# sensormodule.net
KiCad netlist of a schematic drawn in Altium Designer
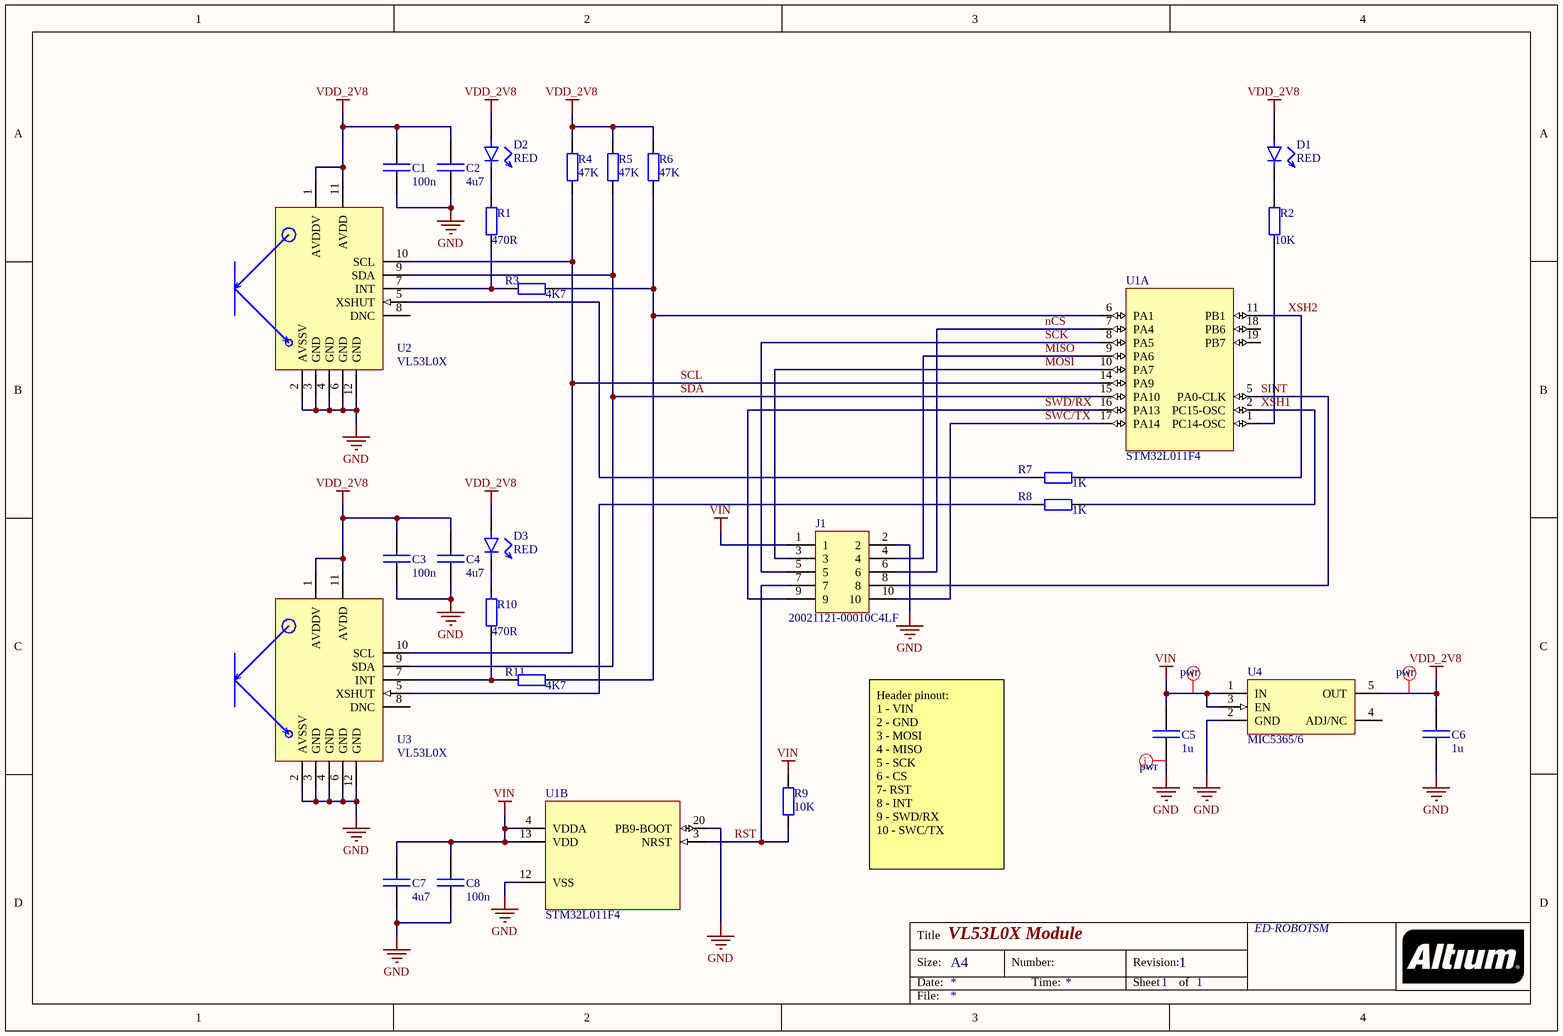
[diagram p0: sensormodule.SchDoc]

(export (version "E")
  (design (tool "Eeschema 10.0.6"))
  (components
    (comp (ref "C1")
      (value "100n")
      (footprint "CAPC1005X06N")
      (description "Capacitor")
      (fields (field (name "Comment") "cap"))
      (libsource (lib "lib_passives") (part "cap"))
    )
    (comp (ref "C2")
      (value "4u7")
      (footprint "CAPC2012X11N")
      (description "Capacitor")
      (fields (field (name "Comment") "cap"))
      (libsource (lib "lib_passives") (part "cap"))
    )
    (comp (ref "C3")
      (value "100n")
      (footprint "CAPC1005X06N")
      (description "Capacitor")
      (fields (field (name "Comment") "cap"))
      (libsource (lib "lib_passives") (part "cap"))
    )
    (comp (ref "C4")
      (value "4u7")
      (footprint "CAPC2012X11N")
      (description "Capacitor")
      (fields (field (name "Comment") "cap"))
      (libsource (lib "lib_passives") (part "cap"))
    )
    (comp (ref "C5")
      (value "1u")
      (footprint "CAPC1005X06N")
      (description "Capacitor")
      (fields (field (name "Comment") "cap"))
      (libsource (lib "lib_passives") (part "cap"))
    )
    (comp (ref "C6")
      (value "1u")
      (footprint "CAPC1005X06N")
      (description "Capacitor")
      (fields (field (name "Comment") "cap"))
      (libsource (lib "lib_passives") (part "cap"))
    )
    (comp (ref "C7")
      (value "4u7")
      (footprint "CAPC2012X11N")
      (description "Capacitor")
      (fields (field (name "Comment") "cap"))
      (libsource (lib "lib_passives") (part "cap"))
    )
    (comp (ref "C8")
      (value "100n")
      (footprint "CAPC1005X06N")
      (description "Capacitor")
      (fields (field (name "Comment") "cap"))
      (libsource (lib "lib_passives") (part "cap"))
    )
    (comp (ref "D1")
      (value "RED")
      (footprint "CAPCP1005X06N")
      (description "LED")
      (fields (field (name "Comment") "led"))
      (libsource (lib "lib_actives") (part "led"))
    )
    (comp (ref "D2")
      (value "RED")
      (footprint "CAPCP1005X06N")
      (description "LED")
      (fields (field (name "Comment") "led"))
      (libsource (lib "lib_actives") (part "led"))
    )
    (comp (ref "D3")
      (value "RED")
      (footprint "CAPCP1005X06N")
      (description "LED")
      (fields (field (name "Comment") "led"))
      (libsource (lib "lib_actives") (part "led"))
    )
    (comp (ref "J1")
      (value "20021121-00010C4LF")
      (footprint "hdr_2x5_50mil")
      (description "2x5 Header")
      (libsource (lib "lib_connectors") (part "hdr_2x5"))
    )
    (comp (ref "R1")
      (value "470R")
      (footprint "RESC1005X04N")
      (description "Resistor")
      (fields (field (name "Comment") "res"))
      (libsource (lib "lib_passives") (part "res"))
    )
    (comp (ref "R2")
      (value "10K")
      (footprint "RESC1005X04N")
      (description "Resistor")
      (fields (field (name "Comment") "res"))
      (libsource (lib "lib_passives") (part "res"))
    )
    (comp (ref "R3")
      (value "4K7")
      (footprint "RESC1005X04N")
      (description "Resistor")
      (fields (field (name "Comment") "res"))
      (libsource (lib "") (part "res_1"))
    )
    (comp (ref "R4")
      (value "47K")
      (footprint "RESC1005X04N")
      (description "Resistor")
      (fields (field (name "Comment") "res"))
      (libsource (lib "lib_passives") (part "res"))
    )
    (comp (ref "R5")
      (value "47K")
      (footprint "RESC1005X04N")
      (description "Resistor")
      (fields (field (name "Comment") "res"))
      (libsource (lib "lib_passives") (part "res"))
    )
    (comp (ref "R6")
      (value "47K")
      (footprint "RESC1005X04N")
      (description "Resistor")
      (fields (field (name "Comment") "res"))
      (libsource (lib "lib_passives") (part "res"))
    )
    (comp (ref "R7")
      (value "1K")
      (footprint "RESC1005X04N")
      (description "Resistor")
      (fields (field (name "Comment") "res"))
      (libsource (lib "") (part "res_1"))
    )
    (comp (ref "R8")
      (value "1K")
      (footprint "RESC1005X04N")
      (description "Resistor")
      (fields (field (name "Comment") "res"))
      (libsource (lib "") (part "res_1"))
    )
    (comp (ref "R9")
      (value "10K")
      (footprint "RESC1005X04N")
      (description "Resistor")
      (fields (field (name "Comment") "res"))
      (libsource (lib "lib_passives") (part "res"))
    )
    (comp (ref "R10")
      (value "470R")
      (footprint "RESC1005X04N")
      (description "Resistor")
      (fields (field (name "Comment") "res"))
      (libsource (lib "lib_passives") (part "res"))
    )
    (comp (ref "R11")
      (value "4K7")
      (footprint "RESC1005X04N")
      (description "Resistor")
      (fields (field (name "Comment") "res"))
      (libsource (lib "") (part "res_1"))
    )
    (comp (ref "U1")
      (value "STM32L011F4")
      (footprint "QFN50P300X300X60-20N")
      (libsource (lib "lib_st") (part "stm32l011f4u"))
    )
    (comp (ref "U2")
      (value "VL53L0X")
      (footprint "LGA12C80P3X5_240X440X105")
      (description "vl53l0x ToF sensor")
      (libsource (lib "sensormodule") (part "vl53l0x"))
    )
    (comp (ref "U3")
      (value "VL53L0X")
      (footprint "LGA12C80P3X5_240X440X105")
      (description "vl53l0x ToF sensor")
      (libsource (lib "sensormodule") (part "vl53l0x"))
    )
    (comp (ref "U4")
      (value "MIC5365/6")
      (footprint "SOT65P210X110-5N")
      (description "5pin voltage regulator")
      (libsource (lib "lib_microchip") (part "mic5365"))
    )
  )
  (nets
    (net (code "1") (name "/MISO") (class "Default")
      (node (ref "J1") (pin "4") (pinfunction "4_4") (pintype "passive"))
      (node (ref "U1") (pin "9") (pinfunction "PA6_9") (pintype "bidirectional"))
    )
    (net (code "2") (name "/MOSI") (class "Default")
      (node (ref "J1") (pin "3") (pinfunction "3_3") (pintype "passive"))
      (node (ref "U1") (pin "10") (pinfunction "PA7_10") (pintype "bidirectional"))
    )
    (net (code "3") (name "/RST") (class "Default")
      (node (ref "J1") (pin "7") (pinfunction "7_7") (pintype "passive"))
      (node (ref "R9") (pin "1") (pinfunction "1_1") (pintype "passive"))
      (node (ref "U1") (pin "3") (pinfunction "NRST_3") (pintype "input"))
    )
    (net (code "4") (name "/SCK") (class "Default")
      (node (ref "J1") (pin "5") (pinfunction "5_5") (pintype "passive"))
      (node (ref "U1") (pin "8") (pinfunction "PA5_8") (pintype "bidirectional"))
    )
    (net (code "5") (name "/SCL") (class "Default")
      (node (ref "R4") (pin "1") (pinfunction "1_1") (pintype "passive"))
      (node (ref "U1") (pin "14") (pinfunction "PA9_14") (pintype "bidirectional"))
      (node (ref "U2") (pin "10") (pinfunction "SCL_10") (pintype "open_collector"))
      (node (ref "U3") (pin "10") (pinfunction "SCL_10") (pintype "open_collector"))
    )
    (net (code "6") (name "/SDA") (class "Default")
      (node (ref "R5") (pin "1") (pinfunction "1_1") (pintype "passive"))
      (node (ref "U1") (pin "15") (pinfunction "PA10_15") (pintype "bidirectional"))
      (node (ref "U2") (pin "9") (pinfunction "SDA_9") (pintype "open_collector"))
      (node (ref "U3") (pin "9") (pinfunction "SDA_9") (pintype "open_collector"))
    )
    (net (code "7") (name "/SINT") (class "Default")
      (node (ref "J1") (pin "8") (pinfunction "8_8") (pintype "passive"))
      (node (ref "U1") (pin "5") (pinfunction "PA0-CLK_5") (pintype "bidirectional"))
    )
    (net (code "8") (name "/SWC{slash}TX") (class "Default")
      (node (ref "J1") (pin "10") (pinfunction "10_10") (pintype "passive"))
      (node (ref "U1") (pin "17") (pinfunction "PA14_17") (pintype "bidirectional"))
    )
    (net (code "9") (name "/SWD{slash}RX") (class "Default")
      (node (ref "J1") (pin "9") (pinfunction "9_9") (pintype "passive"))
      (node (ref "U1") (pin "16") (pinfunction "PA13_16") (pintype "bidirectional"))
    )
    (net (code "10") (name "/XSH1") (class "Default")
      (node (ref "R8") (pin "1") (pinfunction "1_1") (pintype "passive"))
      (node (ref "U1") (pin "2") (pinfunction "PC15-OSC_2") (pintype "bidirectional"))
    )
    (net (code "11") (name "/XSH2") (class "Default")
      (node (ref "R7") (pin "1") (pinfunction "1_1") (pintype "passive"))
      (node (ref "U1") (pin "11") (pinfunction "PB1_11") (pintype "bidirectional"))
    )
    (net (code "12") (name "/nCS") (class "Default")
      (node (ref "J1") (pin "6") (pinfunction "6_6") (pintype "passive"))
      (node (ref "U1") (pin "7") (pinfunction "PA4_7") (pintype "bidirectional"))
    )
    (net (code "13") (name "GND") (class "Default")
      (node (ref "C1") (pin "1") (pinfunction "1_1") (pintype "passive"))
      (node (ref "C2") (pin "1") (pinfunction "1_1") (pintype "passive"))
      (node (ref "C3") (pin "1") (pinfunction "1_1") (pintype "passive"))
      (node (ref "C4") (pin "1") (pinfunction "1_1") (pintype "passive"))
      (node (ref "C5") (pin "1") (pinfunction "1_1") (pintype "passive"))
      (node (ref "C6") (pin "1") (pinfunction "1_1") (pintype "passive"))
      (node (ref "C7") (pin "1") (pinfunction "1_1") (pintype "passive"))
      (node (ref "C8") (pin "1") (pinfunction "1_1") (pintype "passive"))
      (node (ref "J1") (pin "2") (pinfunction "2_2") (pintype "passive"))
      (node (ref "U1") (pin "12") (pinfunction "VSS_12") (pintype "power_in"))
      (node (ref "U1") (pin "20") (pinfunction "PB9-BOOT_20") (pintype "bidirectional"))
      (node (ref "U2") (pin "12") (pinfunction "GND_12") (pintype "power_in"))
      (node (ref "U2") (pin "2") (pinfunction "AVSSV_2") (pintype "power_in"))
      (node (ref "U2") (pin "3") (pinfunction "GND_3") (pintype "power_in"))
      (node (ref "U2") (pin "4") (pinfunction "GND_4") (pintype "power_in"))
      (node (ref "U2") (pin "6") (pinfunction "GND_6") (pintype "power_in"))
      (node (ref "U3") (pin "12") (pinfunction "GND_12") (pintype "power_in"))
      (node (ref "U3") (pin "2") (pinfunction "AVSSV_2") (pintype "power_in"))
      (node (ref "U3") (pin "3") (pinfunction "GND_3") (pintype "power_in"))
      (node (ref "U3") (pin "4") (pinfunction "GND_4") (pintype "power_in"))
      (node (ref "U3") (pin "6") (pinfunction "GND_6") (pintype "power_in"))
      (node (ref "U4") (pin "2") (pinfunction "GND_2") (pintype "power_in"))
    )
    (net (code "14") (name "Net-(D1-PadC)") (class "Default")
      (node (ref "D1") (pin "C") (pinfunction "C_C") (pintype "passive"))
      (node (ref "R2") (pin "2") (pinfunction "2_2") (pintype "passive"))
    )
    (net (code "15") (name "Net-(D2-PadC)") (class "Default")
      (node (ref "D2") (pin "C") (pinfunction "C_C") (pintype "passive"))
      (node (ref "R1") (pin "2") (pinfunction "2_2") (pintype "passive"))
    )
    (net (code "16") (name "Net-(D3-PadC)") (class "Default")
      (node (ref "D3") (pin "C") (pinfunction "C_C") (pintype "passive"))
      (node (ref "R10") (pin "2") (pinfunction "2_2") (pintype "passive"))
    )
    (net (code "17") (name "Net-(U1A-PA1)") (class "Default")
      (node (ref "R11") (pin "1") (pinfunction "1_1") (pintype "passive"))
      (node (ref "R3") (pin "1") (pinfunction "1_1") (pintype "passive"))
      (node (ref "R6") (pin "1") (pinfunction "1_1") (pintype "passive"))
      (node (ref "U1") (pin "6") (pinfunction "PA1_6") (pintype "bidirectional"))
    )
    (net (code "18") (name "Net-(U1A-PC14-OSC)") (class "Default")
      (node (ref "R2") (pin "1") (pinfunction "1_1") (pintype "passive"))
      (node (ref "U1") (pin "1") (pinfunction "PC14-OSC_1") (pintype "bidirectional"))
    )
    (net (code "19") (name "Net-(U2-INT)") (class "Default")
      (node (ref "R1") (pin "1") (pinfunction "1_1") (pintype "passive"))
      (node (ref "R3") (pin "2") (pinfunction "2_2") (pintype "passive"))
      (node (ref "U2") (pin "7") (pinfunction "INT_7") (pintype "open_collector"))
    )
    (net (code "20") (name "Net-(U2-XSHUT)") (class "Default")
      (node (ref "R7") (pin "2") (pinfunction "2_2") (pintype "passive"))
      (node (ref "U2") (pin "5") (pinfunction "XSHUT_5") (pintype "input"))
    )
    (net (code "21") (name "Net-(U3-INT)") (class "Default")
      (node (ref "R10") (pin "1") (pinfunction "1_1") (pintype "passive"))
      (node (ref "R11") (pin "2") (pinfunction "2_2") (pintype "passive"))
      (node (ref "U3") (pin "7") (pinfunction "INT_7") (pintype "open_collector"))
    )
    (net (code "22") (name "Net-(U3-XSHUT)") (class "Default")
      (node (ref "R8") (pin "2") (pinfunction "2_2") (pintype "passive"))
      (node (ref "U3") (pin "5") (pinfunction "XSHUT_5") (pintype "input"))
    )
    (net (code "23") (name "VDD_2V8") (class "Default")
      (node (ref "C1") (pin "2") (pinfunction "2_2") (pintype "passive"))
      (node (ref "C2") (pin "2") (pinfunction "2_2") (pintype "passive"))
      (node (ref "C3") (pin "2") (pinfunction "2_2") (pintype "passive"))
      (node (ref "C4") (pin "2") (pinfunction "2_2") (pintype "passive"))
      (node (ref "C6") (pin "2") (pinfunction "2_2") (pintype "passive"))
      (node (ref "D1") (pin "A") (pinfunction "A_A") (pintype "passive"))
      (node (ref "D2") (pin "A") (pinfunction "A_A") (pintype "passive"))
      (node (ref "D3") (pin "A") (pinfunction "A_A") (pintype "passive"))
      (node (ref "R4") (pin "2") (pinfunction "2_2") (pintype "passive"))
      (node (ref "R5") (pin "2") (pinfunction "2_2") (pintype "passive"))
      (node (ref "R6") (pin "2") (pinfunction "2_2") (pintype "passive"))
      (node (ref "U2") (pin "1") (pinfunction "AVDDV_1") (pintype "power_in"))
      (node (ref "U2") (pin "11") (pinfunction "AVDD_11") (pintype "power_in"))
      (node (ref "U3") (pin "1") (pinfunction "AVDDV_1") (pintype "power_in"))
      (node (ref "U3") (pin "11") (pinfunction "AVDD_11") (pintype "power_in"))
      (node (ref "U4") (pin "5") (pinfunction "OUT_5") (pintype "power_in"))
    )
    (net (code "24") (name "VIN") (class "Default")
      (node (ref "C5") (pin "2") (pinfunction "2_2") (pintype "passive"))
      (node (ref "C7") (pin "2") (pinfunction "2_2") (pintype "passive"))
      (node (ref "C8") (pin "2") (pinfunction "2_2") (pintype "passive"))
      (node (ref "J1") (pin "1") (pinfunction "1_1") (pintype "passive"))
      (node (ref "R9") (pin "2") (pinfunction "2_2") (pintype "passive"))
      (node (ref "U1") (pin "13") (pinfunction "VDD_13") (pintype "power_in"))
      (node (ref "U1") (pin "4") (pinfunction "VDDA_4") (pintype "power_in"))
      (node (ref "U4") (pin "1") (pinfunction "IN_1") (pintype "power_in"))
      (node (ref "U4") (pin "3") (pinfunction "EN_3") (pintype "input"))
    )
    (net (code "25") (name "unconnected-(U1A-PB6-Pad18)") (class "Default")
      (node (ref "U1") (pin "18") (pinfunction "PB6_18") (pintype "bidirectional"))
    )
    (net (code "26") (name "unconnected-(U1A-PB7-Pad19)") (class "Default")
      (node (ref "U1") (pin "19") (pinfunction "PB7_19") (pintype "bidirectional"))
    )
    (net (code "27") (name "unconnected-(U2-DNC-Pad8)") (class "Default")
      (node (ref "U2") (pin "8") (pinfunction "DNC_8") (pintype "passive"))
    )
    (net (code "28") (name "unconnected-(U3-DNC-Pad8)") (class "Default")
      (node (ref "U3") (pin "8") (pinfunction "DNC_8") (pintype "passive"))
    )
    (net (code "29") (name "unconnected-(U4-ADJ{slash}NC-Pad4)") (class "Default")
      (node (ref "U4") (pin "4") (pinfunction "ADJ/NC_4") (pintype "passive"))
    )
  )
)
